# Slaves_Testbench.net
KiCad netlist of a schematic drawn in Altium Designer
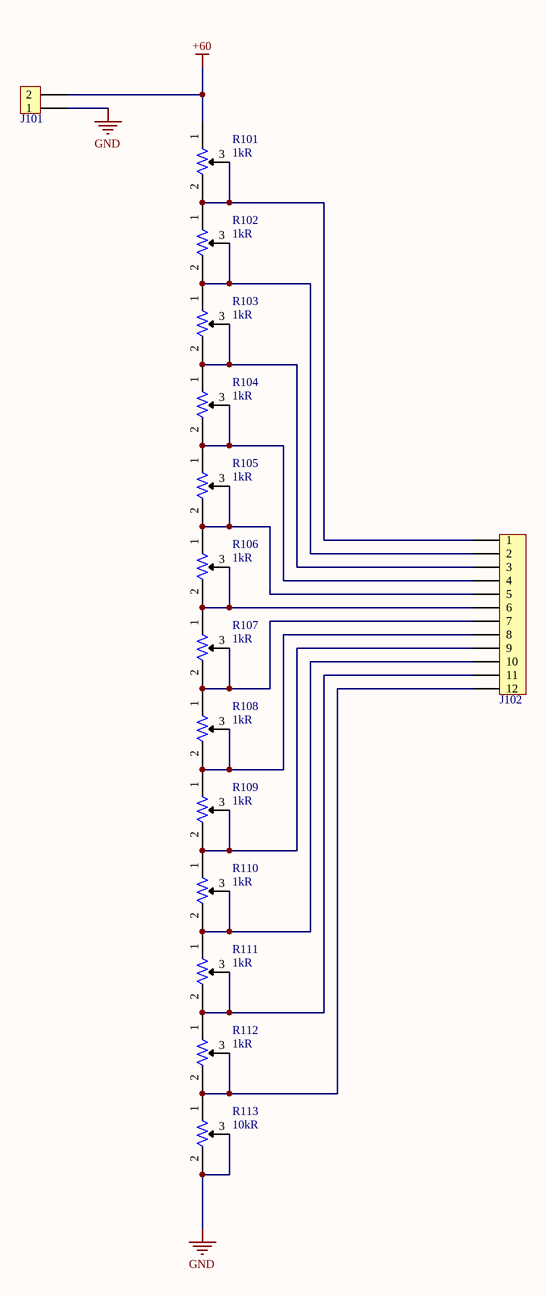
[diagram p0: Slaves_Testbench.SchDoc]

(export (version "E")
  (design (tool "Eeschema 10.0.6"))
  (components
    (comp (ref "J101")
      (value "282836-2")
      (footprint "J_screw_1x2")
      (description "Connector, Terminal Block; Wire Receptacle; 2 Pos.; 16-30 AWG; 0.197 in. CL; Sid")
      (libsource (lib "Electromechanical") (part "J_CON2x1"))
    )
    (comp (ref "J102")
      (value "436501200")
      (footprint "J_MicroFit_1x12")
      (description "Conn Power HDR 12 POS 3mm Solder RA Thru-Hole 12 Terminal 1 Port Micro-Fit 3.0™ Frame")
      (fields (field (name ".CREATOR") "DR"))
      (libsource (lib "Electromechanical") (part "J_MicroFit_1x12"))
    )
    (comp (ref "R101")
      (value "R1k-VTR_RM065")
      (footprint "R-VTR_RM065")
      (description "Generic RM065 1k trimmer")
      (fields (field (name "RESISTANCE") "1kR"))
      (libsource (lib "Passives") (part "R1k-VTR_RM065"))
    )
    (comp (ref "R102")
      (value "R1k-VTR_RM065")
      (footprint "R-VTR_RM065")
      (description "Generic RM065 1k trimmer")
      (fields (field (name "RESISTANCE") "1kR"))
      (libsource (lib "Passives") (part "R1k-VTR_RM065"))
    )
    (comp (ref "R103")
      (value "R1k-VTR_RM065")
      (footprint "R-VTR_RM065")
      (description "Generic RM065 1k trimmer")
      (fields (field (name "RESISTANCE") "1kR"))
      (libsource (lib "Passives") (part "R1k-VTR_RM065"))
    )
    (comp (ref "R104")
      (value "R1k-VTR_RM065")
      (footprint "R-VTR_RM065")
      (description "Generic RM065 1k trimmer")
      (fields (field (name "RESISTANCE") "1kR"))
      (libsource (lib "Passives") (part "R1k-VTR_RM065"))
    )
    (comp (ref "R105")
      (value "R1k-VTR_RM065")
      (footprint "R-VTR_RM065")
      (description "Generic RM065 1k trimmer")
      (fields (field (name "RESISTANCE") "1kR"))
      (libsource (lib "Passives") (part "R1k-VTR_RM065"))
    )
    (comp (ref "R106")
      (value "R1k-VTR_RM065")
      (footprint "R-VTR_RM065")
      (description "Generic RM065 1k trimmer")
      (fields (field (name "RESISTANCE") "1kR"))
      (libsource (lib "Passives") (part "R1k-VTR_RM065"))
    )
    (comp (ref "R107")
      (value "R1k-VTR_RM065")
      (footprint "R-VTR_RM065")
      (description "Generic RM065 1k trimmer")
      (fields (field (name "RESISTANCE") "1kR"))
      (libsource (lib "Passives") (part "R1k-VTR_RM065"))
    )
    (comp (ref "R108")
      (value "R1k-VTR_RM065")
      (footprint "R-VTR_RM065")
      (description "Generic RM065 1k trimmer")
      (fields (field (name "RESISTANCE") "1kR"))
      (libsource (lib "Passives") (part "R1k-VTR_RM065"))
    )
    (comp (ref "R109")
      (value "R1k-VTR_RM065")
      (footprint "R-VTR_RM065")
      (description "Generic RM065 1k trimmer")
      (fields (field (name "RESISTANCE") "1kR"))
      (libsource (lib "Passives") (part "R1k-VTR_RM065"))
    )
    (comp (ref "R110")
      (value "R1k-VTR_RM065")
      (footprint "R-VTR_RM065")
      (description "Generic RM065 1k trimmer")
      (fields (field (name "RESISTANCE") "1kR"))
      (libsource (lib "Passives") (part "R1k-VTR_RM065"))
    )
    (comp (ref "R111")
      (value "R1k-VTR_RM065")
      (footprint "R-VTR_RM065")
      (description "Generic RM065 1k trimmer")
      (fields (field (name "RESISTANCE") "1kR"))
      (libsource (lib "Passives") (part "R1k-VTR_RM065"))
    )
    (comp (ref "R112")
      (value "R1k-VTR_RM065")
      (footprint "R-VTR_RM065")
      (description "Generic RM065 1k trimmer")
      (fields (field (name "RESISTANCE") "1kR"))
      (libsource (lib "Passives") (part "R1k-VTR_RM065"))
    )
    (comp (ref "R113")
      (value "R10k-VTR_RM065")
      (footprint "R-VTR_RM065")
      (description "Generic RM065 1k trimmer")
      (fields (field (name "RESISTANCE") "10kR"))
      (libsource (lib "Passives") (part "R10k-VTR_RM065"))
    )
  )
  (nets
    (net (code "1") (name "+60") (class "Default")
      (node (ref "J101") (pin "2") (pinfunction "2_2") (pintype "passive"))
      (node (ref "R101") (pin "1") (pinfunction "2_1") (pintype "passive"))
    )
    (net (code "2") (name "GND") (class "Default")
      (node (ref "J101") (pin "1") (pinfunction "1_1") (pintype "passive"))
      (node (ref "R113") (pin "2") (pinfunction "2_2") (pintype "passive"))
      (node (ref "R113") (pin "3") (pinfunction "3_3") (pintype "passive"))
    )
    (net (code "3") (name "Net-(J102-Pad1)") (class "Default")
      (node (ref "J102") (pin "1") (pinfunction "1_1") (pintype "passive"))
      (node (ref "R101") (pin "2") (pinfunction "2_2") (pintype "passive"))
      (node (ref "R101") (pin "3") (pinfunction "3_3") (pintype "passive"))
      (node (ref "R102") (pin "1") (pinfunction "2_1") (pintype "passive"))
    )
    (net (code "4") (name "Net-(J102-Pad2)") (class "Default")
      (node (ref "J102") (pin "2") (pinfunction "2_2") (pintype "passive"))
      (node (ref "R102") (pin "2") (pinfunction "2_2") (pintype "passive"))
      (node (ref "R102") (pin "3") (pinfunction "3_3") (pintype "passive"))
      (node (ref "R103") (pin "1") (pinfunction "2_1") (pintype "passive"))
    )
    (net (code "5") (name "Net-(J102-Pad3)") (class "Default")
      (node (ref "J102") (pin "3") (pinfunction "3_3") (pintype "passive"))
      (node (ref "R103") (pin "2") (pinfunction "2_2") (pintype "passive"))
      (node (ref "R103") (pin "3") (pinfunction "3_3") (pintype "passive"))
      (node (ref "R104") (pin "1") (pinfunction "2_1") (pintype "passive"))
    )
    (net (code "6") (name "Net-(J102-Pad4)") (class "Default")
      (node (ref "J102") (pin "4") (pinfunction "4_4") (pintype "passive"))
      (node (ref "R104") (pin "2") (pinfunction "2_2") (pintype "passive"))
      (node (ref "R104") (pin "3") (pinfunction "3_3") (pintype "passive"))
      (node (ref "R105") (pin "1") (pinfunction "2_1") (pintype "passive"))
    )
    (net (code "7") (name "Net-(J102-Pad5)") (class "Default")
      (node (ref "J102") (pin "5") (pinfunction "5_5") (pintype "passive"))
      (node (ref "R105") (pin "2") (pinfunction "2_2") (pintype "passive"))
      (node (ref "R105") (pin "3") (pinfunction "3_3") (pintype "passive"))
      (node (ref "R106") (pin "1") (pinfunction "2_1") (pintype "passive"))
    )
    (net (code "8") (name "Net-(J102-Pad6)") (class "Default")
      (node (ref "J102") (pin "6") (pinfunction "6_6") (pintype "passive"))
      (node (ref "R106") (pin "2") (pinfunction "2_2") (pintype "passive"))
      (node (ref "R106") (pin "3") (pinfunction "3_3") (pintype "passive"))
      (node (ref "R107") (pin "1") (pinfunction "2_1") (pintype "passive"))
    )
    (net (code "9") (name "Net-(J102-Pad7)") (class "Default")
      (node (ref "J102") (pin "7") (pinfunction "7_7") (pintype "passive"))
      (node (ref "R107") (pin "2") (pinfunction "2_2") (pintype "passive"))
      (node (ref "R107") (pin "3") (pinfunction "3_3") (pintype "passive"))
      (node (ref "R108") (pin "1") (pinfunction "2_1") (pintype "passive"))
    )
    (net (code "10") (name "Net-(J102-Pad8)") (class "Default")
      (node (ref "J102") (pin "8") (pinfunction "8_8") (pintype "passive"))
      (node (ref "R108") (pin "2") (pinfunction "2_2") (pintype "passive"))
      (node (ref "R108") (pin "3") (pinfunction "3_3") (pintype "passive"))
      (node (ref "R109") (pin "1") (pinfunction "2_1") (pintype "passive"))
    )
    (net (code "11") (name "Net-(J102-Pad9)") (class "Default")
      (node (ref "J102") (pin "9") (pinfunction "9_9") (pintype "passive"))
      (node (ref "R109") (pin "2") (pinfunction "2_2") (pintype "passive"))
      (node (ref "R109") (pin "3") (pinfunction "3_3") (pintype "passive"))
      (node (ref "R110") (pin "1") (pinfunction "2_1") (pintype "passive"))
    )
    (net (code "12") (name "Net-(J102-Pad10)") (class "Default")
      (node (ref "J102") (pin "10") (pinfunction "10_10") (pintype "passive"))
      (node (ref "R110") (pin "2") (pinfunction "2_2") (pintype "passive"))
      (node (ref "R110") (pin "3") (pinfunction "3_3") (pintype "passive"))
      (node (ref "R111") (pin "1") (pinfunction "2_1") (pintype "passive"))
    )
    (net (code "13") (name "Net-(J102-Pad11)") (class "Default")
      (node (ref "J102") (pin "11") (pinfunction "11_11") (pintype "passive"))
      (node (ref "R111") (pin "2") (pinfunction "2_2") (pintype "passive"))
      (node (ref "R111") (pin "3") (pinfunction "3_3") (pintype "passive"))
      (node (ref "R112") (pin "1") (pinfunction "2_1") (pintype "passive"))
    )
    (net (code "14") (name "Net-(J102-Pad12)") (class "Default")
      (node (ref "J102") (pin "12") (pinfunction "12_12") (pintype "passive"))
      (node (ref "R112") (pin "2") (pinfunction "2_2") (pintype "passive"))
      (node (ref "R112") (pin "3") (pinfunction "3_3") (pintype "passive"))
      (node (ref "R113") (pin "1") (pinfunction "2_1") (pintype "passive"))
    )
  )
)
